# Spartan3_TestBoard.net
KiCad netlist of a schematic drawn in Altium Designer
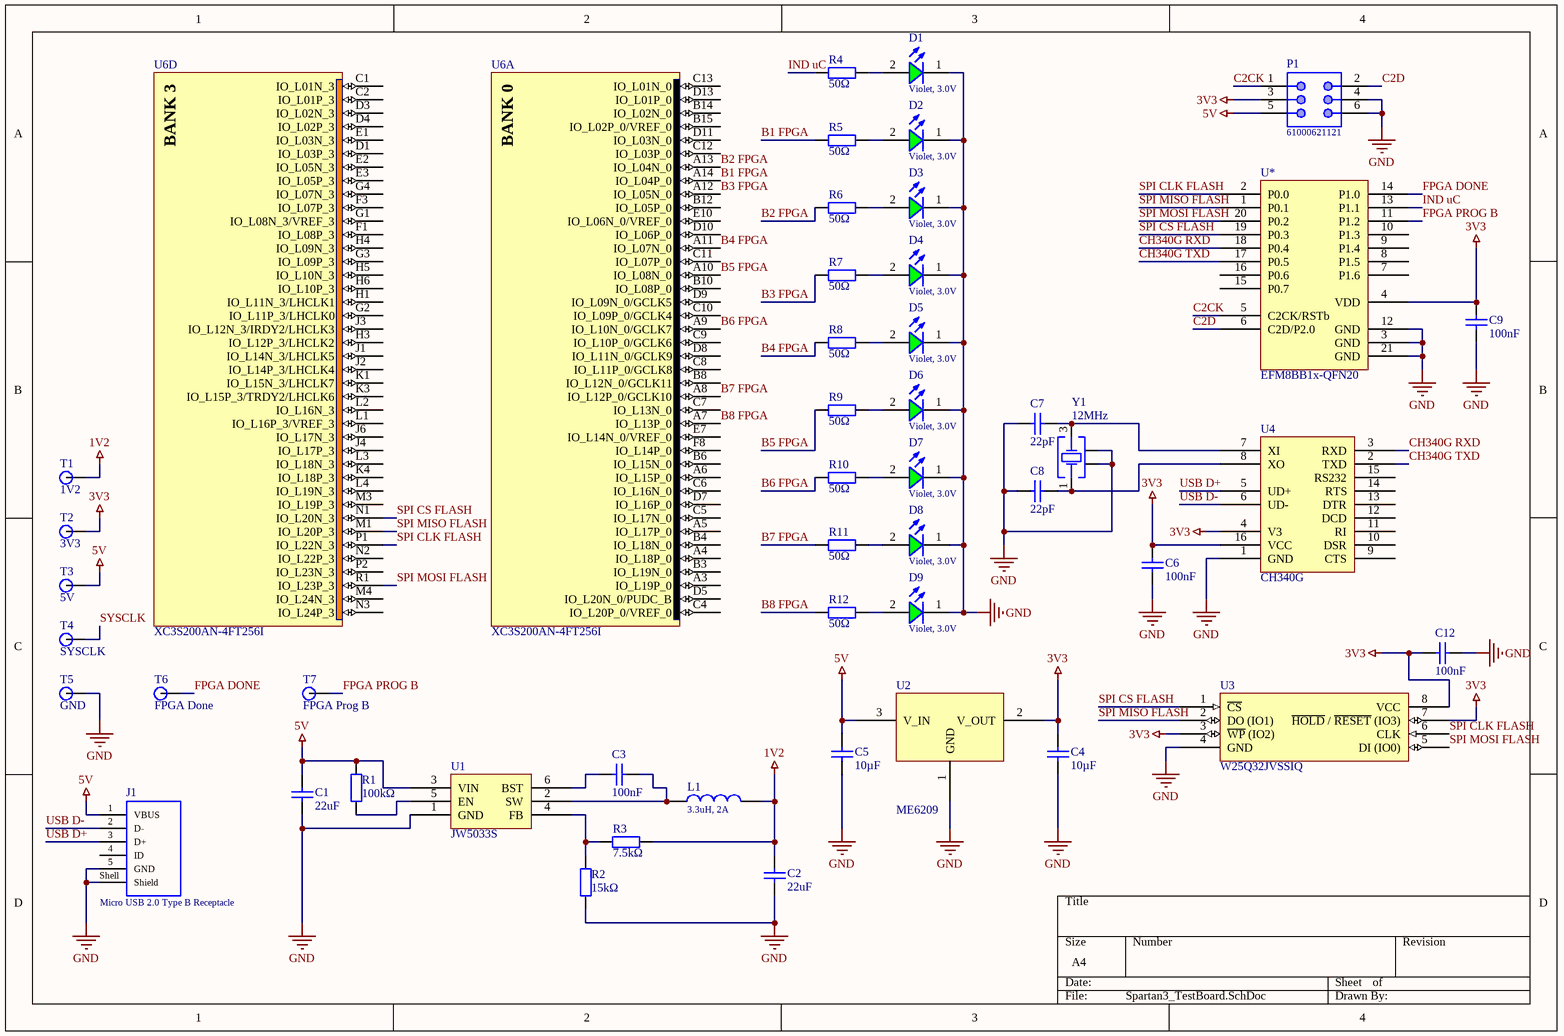
[diagram p0: Spartan3_TestBoard.SchDoc]

(export (version "E")
  (design (tool "Eeschema 10.0.6"))
  (components
    (comp (ref "C1")
      (value "22uF")
      (footprint "WCAP-CSGP_0805_H=0.8mm_Reflow")
      (description "WCAP-CSGP General Purpose Ceramic Capacitors, size 0805, 1.5nF, +/-5%, 16VDC")
      (fields (field (name "PART NUMBER") "885012007022") (field (name "PUBLISHER") "Wurth Elektronik"))
      (libsource (lib "Altium_WCAP-CSGP (rev19a)") (part "885012007022"))
    )
    (comp (ref "C2")
      (value "22uF")
      (footprint "WCAP-CSGP_0805_H=0.8mm_Reflow")
      (description "WCAP-CSGP General Purpose Ceramic Capacitors, size 0805, 1.5nF, +/-5%, 16VDC")
      (fields (field (name "PART NUMBER") "885012007022") (field (name "PUBLISHER") "Wurth Elektronik"))
      (libsource (lib "Altium_WCAP-CSGP (rev19a)") (part "885012007022"))
    )
    (comp (ref "C3")
      (value "100nF")
      (footprint "WCAP-CSGP_0402")
      (description "WCAP-CSGP General Purpose Ceramic Capacitors, size 0402, 100nF, +/-10%, 10VDC")
      (fields (field (name "PART NUMBER") "885012205018") (field (name "PUBLISHER") "Wurth Elektronik"))
      (libsource (lib "Altium_WCAP-CSGP (rev19a)") (part "885012205018"))
    )
    (comp (ref "C4")
      (value "10µF")
      (footprint "WCAP-CSGP_0402")
      (description "WCAP-CSGP General Purpose Ceramic Capacitors, size 0402, 100nF, +/-10%, 10VDC")
      (fields (field (name "PART NUMBER") "885012205018") (field (name "PUBLISHER") "Wurth Elektronik"))
      (libsource (lib "Altium_WCAP-CSGP (rev19a)") (part "885012205018"))
    )
    (comp (ref "C5")
      (value "10µF")
      (footprint "WCAP-CSGP_0402")
      (description "WCAP-CSGP General Purpose Ceramic Capacitors, size 0402, 100nF, +/-10%, 10VDC")
      (fields (field (name "PART NUMBER") "885012205018") (field (name "PUBLISHER") "Wurth Elektronik"))
      (libsource (lib "Altium_WCAP-CSGP (rev19a)") (part "885012205018"))
    )
    (comp (ref "C6")
      (value "100nF")
      (footprint "WCAP-CSGP_0402")
      (description "WCAP-CSGP General Purpose Ceramic Capacitors, size 0402, 100nF, +/-10%, 10VDC")
      (fields (field (name "PART NUMBER") "885012205018") (field (name "PUBLISHER") "Wurth Elektronik"))
      (libsource (lib "Altium_WCAP-CSGP (rev19a)") (part "885012205018"))
    )
    (comp (ref "C7")
      (value "22pF")
      (footprint "WCAP-CSGP_0402")
      (description "WCAP-CSGP General Purpose Ceramic Capacitors, size 0402, 100nF, +/-10%, 10VDC")
      (fields (field (name "PART NUMBER") "885012205018") (field (name "PUBLISHER") "Wurth Elektronik"))
      (libsource (lib "Altium_WCAP-CSGP (rev19a)") (part "885012205018"))
    )
    (comp (ref "C8")
      (value "22pF")
      (footprint "WCAP-CSGP_0402")
      (description "WCAP-CSGP General Purpose Ceramic Capacitors, size 0402, 100nF, +/-10%, 10VDC")
      (fields (field (name "PART NUMBER") "885012205018") (field (name "PUBLISHER") "Wurth Elektronik"))
      (libsource (lib "Altium_WCAP-CSGP (rev19a)") (part "885012205018"))
    )
    (comp (ref "C9")
      (value "100nF")
      (footprint "WCAP-CSGP_0402")
      (description "WCAP-CSGP General Purpose Ceramic Capacitors, size 0402, 100nF, +/-10%, 10VDC")
      (fields (field (name "PART NUMBER") "885012205018") (field (name "PUBLISHER") "Wurth Elektronik"))
      (libsource (lib "Altium_WCAP-CSGP (rev19a)") (part "885012205018"))
    )
    (comp (ref "C12")
      (value "100nF")
      (footprint "WCAP-CSGP_0402")
      (description "WCAP-CSGP General Purpose Ceramic Capacitors, size 0402, 100nF, +/-10%, 10VDC")
      (fields (field (name "PART NUMBER") "885012205018") (field (name "PUBLISHER") "Wurth Elektronik"))
      (libsource (lib "Altium_WCAP-CSGP (rev19a)") (part "885012205018"))
    )
    (comp (ref "D1")
      (value "Violet, 3.0V")
      (footprint "WL-SMCW_0603_H=0.7mm")
      (description "WL-SMCW SMT Mono-color Chip LED Waterclear, size 0603, Green, 3.2V, 140deg")
      (fields (field (name "PART NUMBER") "150060GS75000") (field (name "PUBLISHER") "Wurth Elektronik"))
      (libsource (lib "150060BS75000_Altium_WL-SMCW_rev20a") (part "150060GS75000"))
    )
    (comp (ref "D2")
      (value "Violet, 3.0V")
      (footprint "WL-SMCW_0603_H=0.7mm")
      (description "WL-SMCW SMT Mono-color Chip LED Waterclear, size 0603, Green, 3.2V, 140deg")
      (fields (field (name "PART NUMBER") "150060GS75000") (field (name "PUBLISHER") "Wurth Elektronik"))
      (libsource (lib "150060BS75000_Altium_WL-SMCW_rev20a") (part "150060GS75000"))
    )
    (comp (ref "D3")
      (value "Violet, 3.0V")
      (footprint "WL-SMCW_0603_H=0.7mm")
      (description "WL-SMCW SMT Mono-color Chip LED Waterclear, size 0603, Green, 3.2V, 140deg")
      (fields (field (name "PART NUMBER") "150060GS75000") (field (name "PUBLISHER") "Wurth Elektronik"))
      (libsource (lib "150060BS75000_Altium_WL-SMCW_rev20a") (part "150060GS75000"))
    )
    (comp (ref "D4")
      (value "Violet, 3.0V")
      (footprint "WL-SMCW_0603_H=0.7mm")
      (description "WL-SMCW SMT Mono-color Chip LED Waterclear, size 0603, Green, 3.2V, 140deg")
      (fields (field (name "PART NUMBER") "150060GS75000") (field (name "PUBLISHER") "Wurth Elektronik"))
      (libsource (lib "150060BS75000_Altium_WL-SMCW_rev20a") (part "150060GS75000"))
    )
    (comp (ref "D5")
      (value "Violet, 3.0V")
      (footprint "WL-SMCW_0603_H=0.7mm")
      (description "WL-SMCW SMT Mono-color Chip LED Waterclear, size 0603, Green, 3.2V, 140deg")
      (fields (field (name "PART NUMBER") "150060GS75000") (field (name "PUBLISHER") "Wurth Elektronik"))
      (libsource (lib "150060BS75000_Altium_WL-SMCW_rev20a") (part "150060GS75000"))
    )
    (comp (ref "D6")
      (value "Violet, 3.0V")
      (footprint "WL-SMCW_0603_H=0.7mm")
      (description "WL-SMCW SMT Mono-color Chip LED Waterclear, size 0603, Green, 3.2V, 140deg")
      (fields (field (name "PART NUMBER") "150060GS75000") (field (name "PUBLISHER") "Wurth Elektronik"))
      (libsource (lib "150060BS75000_Altium_WL-SMCW_rev20a") (part "150060GS75000"))
    )
    (comp (ref "D7")
      (value "Violet, 3.0V")
      (footprint "WL-SMCW_0603_H=0.7mm")
      (description "WL-SMCW SMT Mono-color Chip LED Waterclear, size 0603, Green, 3.2V, 140deg")
      (fields (field (name "PART NUMBER") "150060GS75000") (field (name "PUBLISHER") "Wurth Elektronik"))
      (libsource (lib "150060BS75000_Altium_WL-SMCW_rev20a") (part "150060GS75000"))
    )
    (comp (ref "D8")
      (value "Violet, 3.0V")
      (footprint "WL-SMCW_0603_H=0.7mm")
      (description "WL-SMCW SMT Mono-color Chip LED Waterclear, size 0603, Green, 3.2V, 140deg")
      (fields (field (name "PART NUMBER") "150060GS75000") (field (name "PUBLISHER") "Wurth Elektronik"))
      (libsource (lib "150060BS75000_Altium_WL-SMCW_rev20a") (part "150060GS75000"))
    )
    (comp (ref "D9")
      (value "Violet, 3.0V")
      (footprint "WL-SMCW_0603_H=0.7mm")
      (description "WL-SMCW SMT Mono-color Chip LED Waterclear, size 0603, Green, 3.2V, 140deg")
      (fields (field (name "PART NUMBER") "150060GS75000") (field (name "PUBLISHER") "Wurth Elektronik"))
      (libsource (lib "150060BS75000_Altium_WL-SMCW_rev20a") (part "150060GS75000"))
    )
    (comp (ref "J1")
      (value "Micro USB 2.0 Type B Receptacle")
      (footprint "629105136821")
      (description "Micro USB 2.0 Type B, Receptacle, Horizontal, SMT")
      (fields
        (field (name "MANUFACTURER") "Wurth Elektronik")
        (field (name "MANUFACTURER PART NUMBER") "629105136821")
      )
      (libsource (lib "Altium_WR-USB (rev21a)") (part "629105136821"))
    )
    (comp (ref "L1")
      (value "3.3uH, 2A")
      (footprint "WE-PD2_5848")
      (description "WE-PD2 SMT Power Inductor, size 5848, 3.3uH, 4A")
      (fields
        (field (name "MANUFACTURER") "Wurth Elektronik")
        (field (name "MANUFACTURER PART NUMBER") "744774033")
      )
      (libsource (lib "744774022_Altium_WE-PD2_rev20a") (part "744774033"))
    )
    (comp (ref "P1")
      (value "61000621121")
      (footprint "61000621121")
      (description "WR-PHD Pin Header, SMT, pitch 2.54mm, Dual Row, Vertical, 6p")
      (fields (field (name "MANUFACTURER") "Wurth Elektronik"))
      (libsource (lib "Altium_WR-PHD (rev20a)") (part "61000621121"))
    )
    (comp (ref "R1")
      (value "100kΩ")
      (footprint "WRIS-PSMB_0805_H=0.35mm")
      (description "WRIS-PSMB Metal Plate Resistors, size 0805, 5mOhm, +/-1%, 0.5W")
      (fields (field (name "PART NUMBER") "580060720003") (field (name "PUBLISHER") "Wurth Elektronik"))
      (libsource (lib "") (part "580060720003_1"))
    )
    (comp (ref "R2")
      (value "15kΩ")
      (footprint "WRIS-PSMB_0805_H=0.35mm")
      (description "WRIS-PSMB Metal Plate Resistors, size 0805, 5mOhm, +/-1%, 0.5W")
      (fields (field (name "PART NUMBER") "580060720003") (field (name "PUBLISHER") "Wurth Elektronik"))
      (libsource (lib "") (part "580060720003_2"))
    )
    (comp (ref "R3")
      (value "7.5kΩ")
      (footprint "WRIS-PSMB_0805_H=0.35mm")
      (description "WRIS-PSMB Metal Plate Resistors, size 0805, 5mOhm, +/-1%, 0.5W")
      (fields (field (name "PART NUMBER") "580060720003") (field (name "PUBLISHER") "Wurth Elektronik"))
      (libsource (lib "Altium_WRIS-PSMB (rev19a)") (part "580060720003"))
    )
    (comp (ref "R4")
      (value "50Ω")
      (footprint "WRIS-PSMB_0805_H=0.35mm")
      (description "WRIS-PSMB Metal Plate Resistors, size 0805, 5mOhm, +/-1%, 0.5W")
      (fields (field (name "PART NUMBER") "580060720003") (field (name "PUBLISHER") "Wurth Elektronik"))
      (libsource (lib "Altium_WRIS-PSMB (rev19a)") (part "580060720003"))
    )
    (comp (ref "R5")
      (value "50Ω")
      (footprint "WRIS-PSMB_0805_H=0.35mm")
      (description "WRIS-PSMB Metal Plate Resistors, size 0805, 5mOhm, +/-1%, 0.5W")
      (fields (field (name "PART NUMBER") "580060720003") (field (name "PUBLISHER") "Wurth Elektronik"))
      (libsource (lib "Altium_WRIS-PSMB (rev19a)") (part "580060720003"))
    )
    (comp (ref "R6")
      (value "50Ω")
      (footprint "WRIS-PSMB_0805_H=0.35mm")
      (description "WRIS-PSMB Metal Plate Resistors, size 0805, 5mOhm, +/-1%, 0.5W")
      (fields (field (name "PART NUMBER") "580060720003") (field (name "PUBLISHER") "Wurth Elektronik"))
      (libsource (lib "Altium_WRIS-PSMB (rev19a)") (part "580060720003"))
    )
    (comp (ref "R7")
      (value "50Ω")
      (footprint "WRIS-PSMB_0805_H=0.35mm")
      (description "WRIS-PSMB Metal Plate Resistors, size 0805, 5mOhm, +/-1%, 0.5W")
      (fields (field (name "PART NUMBER") "580060720003") (field (name "PUBLISHER") "Wurth Elektronik"))
      (libsource (lib "Altium_WRIS-PSMB (rev19a)") (part "580060720003"))
    )
    (comp (ref "R8")
      (value "50Ω")
      (footprint "WRIS-PSMB_0805_H=0.35mm")
      (description "WRIS-PSMB Metal Plate Resistors, size 0805, 5mOhm, +/-1%, 0.5W")
      (fields (field (name "PART NUMBER") "580060720003") (field (name "PUBLISHER") "Wurth Elektronik"))
      (libsource (lib "Altium_WRIS-PSMB (rev19a)") (part "580060720003"))
    )
    (comp (ref "R9")
      (value "50Ω")
      (footprint "WRIS-PSMB_0805_H=0.35mm")
      (description "WRIS-PSMB Metal Plate Resistors, size 0805, 5mOhm, +/-1%, 0.5W")
      (fields (field (name "PART NUMBER") "580060720003") (field (name "PUBLISHER") "Wurth Elektronik"))
      (libsource (lib "Altium_WRIS-PSMB (rev19a)") (part "580060720003"))
    )
    (comp (ref "R10")
      (value "50Ω")
      (footprint "WRIS-PSMB_0805_H=0.35mm")
      (description "WRIS-PSMB Metal Plate Resistors, size 0805, 5mOhm, +/-1%, 0.5W")
      (fields (field (name "PART NUMBER") "580060720003") (field (name "PUBLISHER") "Wurth Elektronik"))
      (libsource (lib "Altium_WRIS-PSMB (rev19a)") (part "580060720003"))
    )
    (comp (ref "R11")
      (value "50Ω")
      (footprint "WRIS-PSMB_0805_H=0.35mm")
      (description "WRIS-PSMB Metal Plate Resistors, size 0805, 5mOhm, +/-1%, 0.5W")
      (fields (field (name "PART NUMBER") "580060720003") (field (name "PUBLISHER") "Wurth Elektronik"))
      (libsource (lib "Altium_WRIS-PSMB (rev19a)") (part "580060720003"))
    )
    (comp (ref "R12")
      (value "50Ω")
      (footprint "WRIS-PSMB_0805_H=0.35mm")
      (description "WRIS-PSMB Metal Plate Resistors, size 0805, 5mOhm, +/-1%, 0.5W")
      (fields (field (name "PART NUMBER") "580060720003") (field (name "PUBLISHER") "Wurth Elektronik"))
      (libsource (lib "Altium_WRIS-PSMB (rev19a)") (part "580060720003"))
    )
    (comp (ref "T1") (value "1V2") (footprint "Testpoint") (libsource (lib "Testpoint") (part "Testpoint")))
    (comp (ref "T2") (value "3V3") (footprint "Testpoint") (libsource (lib "Testpoint") (part "Testpoint")))
    (comp (ref "T3") (value "5V") (footprint "Testpoint") (libsource (lib "Testpoint") (part "Testpoint")))
    (comp (ref "T4")
      (value "SYSCLK")
      (footprint "Testpoint")
      (libsource (lib "Testpoint") (part "Testpoint"))
    )
    (comp (ref "T5") (value "GND") (footprint "Testpoint") (libsource (lib "Testpoint") (part "Testpoint")))
    (comp (ref "T6")
      (value "FPGA Done")
      (footprint "Testpoint")
      (libsource (lib "Testpoint") (part "Testpoint"))
    )
    (comp (ref "T7")
      (value "FPGA Prog B")
      (footprint "Testpoint")
      (libsource (lib "Testpoint") (part "Testpoint"))
    )
    (comp (ref "U*")
      (value "EFM8BB1x-QFN20")
      (footprint "*QFN50P300X300X80-21N")
      (libsource (lib "EFM8BB1x_QFN20") (part "EFM8BB1x-QFN20"))
    )
    (comp (ref "U1")
      (value "JW5033S")
      (footprint "SOT95P280X110-6N")
      (description "2A Step-Down Converter")
      (libsource (lib "JW5033S") (part "JW5033S"))
    )
    (comp (ref "U2")
      (value "ME6209")
      (footprint "SOT95P285X150-3N")
      (libsource (lib "ME6209") (part "ME6209"))
    )
    (comp (ref "U3")
      (value "W25Q32JVSSIQ")
      (footprint "W25Q32JVSSIQ")
      (description "IC FLASH 32MBIT SPI/QUAD 8SOIC")
      (libsource (lib "W25Q32JVSSIQ") (part "W25Q32JVSSIQ"))
    )
    (comp (ref "U4") (value "CH340G") (footprint "CH340G") (libsource (lib "CH340G") (part "CH340G")))
    (comp (ref "U6")
      (value "XC3S200AN-4FT256I")
      (footprint "XC3S200AN-4FT256I")
      (libsource (lib "XC3S200AN-4FT256I") (part "XC3S200AN-4FT256I"))
    )
    (comp (ref "Y1")
      (value "12MHz")
      (footprint "WE-XTAL_CFPX-180")
      (description "WE-XTAL Quartz Crystal, SMT, CFPX-180, 12MHz, +/-20ppm")
      (fields
        (field (name "MANUFACTURER PART NUMBER") "830055295")
        (field (name "MANUFACTURER") "Wurth Elektronik")
      )
      (libsource (lib "Altium_WE-XTAL (rev21a)") (part "830055295"))
    )
  )
  (nets
    (net (code "1") (name "/B1 FPGA") (class "Default")
      (node (ref "R5") (pin "1") (pinfunction "1_1") (pintype "passive"))
      (node (ref "U6") (pin "A14") (pinfunction "IO_L04P_0_A14") (pintype "bidirectional"))
    )
    (net (code "2") (name "/B2 FPGA") (class "Default")
      (node (ref "R6") (pin "1") (pinfunction "1_1") (pintype "passive"))
      (node (ref "U6") (pin "A13") (pinfunction "IO_L04N_0_A13") (pintype "bidirectional"))
    )
    (net (code "3") (name "/B3 FPGA") (class "Default")
      (node (ref "R7") (pin "1") (pinfunction "1_1") (pintype "passive"))
      (node (ref "U6") (pin "A12") (pinfunction "IO_L05N_0_A12") (pintype "bidirectional"))
    )
    (net (code "4") (name "/B4 FPGA") (class "Default")
      (node (ref "R8") (pin "1") (pinfunction "1_1") (pintype "passive"))
      (node (ref "U6") (pin "A11") (pinfunction "IO_L07N_0_A11") (pintype "bidirectional"))
    )
    (net (code "5") (name "/B5 FPGA") (class "Default")
      (node (ref "R9") (pin "1") (pinfunction "1_1") (pintype "passive"))
      (node (ref "U6") (pin "A10") (pinfunction "IO_L08N_0_A10") (pintype "bidirectional"))
    )
    (net (code "6") (name "/B6 FPGA") (class "Default")
      (node (ref "R10") (pin "1") (pinfunction "1_1") (pintype "passive"))
      (node (ref "U6") (pin "A9") (pinfunction "IO_L10N_0/GCLK7_A9") (pintype "bidirectional"))
    )
    (net (code "7") (name "/B7 FPGA") (class "Default")
      (node (ref "R11") (pin "1") (pinfunction "1_1") (pintype "passive"))
      (node (ref "U6") (pin "A8") (pinfunction "IO_L12P_0/GCLK10_A8") (pintype "bidirectional"))
    )
    (net (code "8") (name "/B8 FPGA") (class "Default")
      (node (ref "R12") (pin "1") (pinfunction "1_1") (pintype "passive"))
      (node (ref "U6") (pin "A7") (pinfunction "IO_L13P_0_A7") (pintype "bidirectional"))
    )
    (net (code "9") (name "/C2CK") (class "Default")
      (node (ref "P1") (pin "1") (pinfunction "1_1") (pintype "passive"))
      (node (ref "U*") (pin "5") (pinfunction "C2CK/RSTb_5") (pintype "passive"))
    )
    (net (code "10") (name "/C2D") (class "Default")
      (node (ref "P1") (pin "2") (pinfunction "2_2") (pintype "passive"))
      (node (ref "U*") (pin "6") (pinfunction "C2D/P2.0_6") (pintype "passive"))
    )
    (net (code "11") (name "/CH340G RXD") (class "Default")
      (node (ref "U*") (pin "18") (pinfunction "P0.4_18") (pintype "passive"))
      (node (ref "U4") (pin "3") (pinfunction "RXD_3") (pintype "passive"))
    )
    (net (code "12") (name "/CH340G TXD") (class "Default")
      (node (ref "U*") (pin "17") (pinfunction "P0.5_17") (pintype "passive"))
      (node (ref "U4") (pin "2") (pinfunction "TXD_2") (pintype "passive"))
    )
    (net (code "13") (name "/FPGA DONE") (class "Default")
      (node (ref "T6") (pin "1") (pinfunction "1_1") (pintype "passive"))
      (node (ref "U*") (pin "14") (pinfunction "P1.0_14") (pintype "passive"))
    )
    (net (code "14") (name "/FPGA PROG B") (class "Default")
      (node (ref "T7") (pin "1") (pinfunction "1_1") (pintype "passive"))
      (node (ref "U*") (pin "11") (pinfunction "P1.2_11") (pintype "passive"))
    )
    (net (code "15") (name "/IND uC") (class "Default")
      (node (ref "R4") (pin "1") (pinfunction "1_1") (pintype "passive"))
      (node (ref "U*") (pin "13") (pinfunction "P1.1_13") (pintype "passive"))
    )
    (net (code "16") (name "/SPI CLK FLASH") (class "Default")
      (node (ref "U*") (pin "2") (pinfunction "P0.0_2") (pintype "passive"))
      (node (ref "U3") (pin "6") (pinfunction "CLK_6") (pintype "input"))
      (node (ref "U6") (pin "P1") (pinfunction "IO_L22N_3_P1") (pintype "bidirectional"))
    )
    (net (code "17") (name "/SPI CS FLASH") (class "Default")
      (node (ref "U*") (pin "19") (pinfunction "P0.3_19") (pintype "passive"))
      (node (ref "U3") (pin "1") (pinfunction "~{CS}_1") (pintype "input"))
      (node (ref "U6") (pin "N1") (pinfunction "IO_L20N_3_N1") (pintype "bidirectional"))
    )
    (net (code "18") (name "/SPI MISO FLASH") (class "Default")
      (node (ref "U*") (pin "1") (pinfunction "P0.1_1") (pintype "passive"))
      (node (ref "U3") (pin "2") (pinfunction "DO_(IO1)_2") (pintype "bidirectional"))
      (node (ref "U6") (pin "M1") (pinfunction "IO_L20P_3_M1") (pintype "bidirectional"))
    )
    (net (code "19") (name "/SPI MOSI FLASH") (class "Default")
      (node (ref "U*") (pin "20") (pinfunction "P0.2_20") (pintype "passive"))
      (node (ref "U3") (pin "5") (pinfunction "DI_(IO0)_5") (pintype "bidirectional"))
      (node (ref "U6") (pin "R1") (pinfunction "IO_L23P_3_R1") (pintype "bidirectional"))
    )
    (net (code "20") (name "/SYSCLK") (class "Default")
      (node (ref "T4") (pin "1") (pinfunction "1_1") (pintype "passive"))
    )
    (net (code "21") (name "/USB D+") (class "Default")
      (node (ref "J1") (pin "3") (pinfunction "D+_3") (pintype "passive"))
      (node (ref "U4") (pin "5") (pinfunction "UD+_5") (pintype "passive"))
    )
    (net (code "22") (name "/USB D-") (class "Default")
      (node (ref "J1") (pin "2") (pinfunction "D-_2") (pintype "passive"))
      (node (ref "U4") (pin "6") (pinfunction "UD-_6") (pintype "passive"))
    )
    (net (code "23") (name "1V2") (class "Default")
      (node (ref "C2") (pin "2") (pinfunction "2_2") (pintype "passive"))
      (node (ref "L1") (pin "2") (pinfunction "2_2") (pintype "passive"))
      (node (ref "R3") (pin "2") (pinfunction "2_2") (pintype "passive"))
      (node (ref "T1") (pin "1") (pinfunction "1_1") (pintype "passive"))
    )
    (net (code "24") (name "3V3") (class "Default")
      (node (ref "C12") (pin "1") (pinfunction "1_1") (pintype "passive"))
      (node (ref "C4") (pin "2") (pinfunction "2_2") (pintype "passive"))
      (node (ref "C6") (pin "2") (pinfunction "2_2") (pintype "passive"))
      (node (ref "C9") (pin "1") (pinfunction "1_1") (pintype "passive"))
      (node (ref "P1") (pin "3") (pinfunction "3_3") (pintype "passive"))
      (node (ref "T2") (pin "1") (pinfunction "1_1") (pintype "passive"))
      (node (ref "U*") (pin "4") (pinfunction "VDD_4") (pintype "passive"))
      (node (ref "U2") (pin "2") (pinfunction "V_OUT_2") (pintype "passive"))
      (node (ref "U3") (pin "3") (pinfunction "~{WP}_(IO2)_3") (pintype "bidirectional"))
      (node (ref "U3") (pin "7") (pinfunction "~{HOLD}_/_~{RESET}_(IO3)_7") (pintype "bidirectional"))
      (node (ref "U3") (pin "8") (pinfunction "VCC_8") (pintype "power_in"))
      (node (ref "U4") (pin "16") (pinfunction "VCC_16") (pintype "passive"))
      (node (ref "U4") (pin "4") (pinfunction "V3_4") (pintype "passive"))
    )
    (net (code "25") (name "5V") (class "Default")
      (node (ref "C1") (pin "2") (pinfunction "2_2") (pintype "passive"))
      (node (ref "C5") (pin "2") (pinfunction "2_2") (pintype "passive"))
      (node (ref "J1") (pin "1") (pinfunction "VBUS_1") (pintype "passive"))
      (node (ref "P1") (pin "5") (pinfunction "5_5") (pintype "passive"))
      (node (ref "R1") (pin "1") (pinfunction "1_1") (pintype "passive"))
      (node (ref "T3") (pin "1") (pinfunction "1_1") (pintype "passive"))
      (node (ref "U1") (pin "3") (pinfunction "VIN_3") (pintype "passive"))
      (node (ref "U2") (pin "3") (pinfunction "V_IN_3") (pintype "passive"))
    )
    (net (code "26") (name "GND") (class "Default")
      (node (ref "C1") (pin "1") (pinfunction "1_1") (pintype "passive"))
      (node (ref "C12") (pin "2") (pinfunction "2_2") (pintype "passive"))
      (node (ref "C2") (pin "1") (pinfunction "1_1") (pintype "passive"))
      (node (ref "C4") (pin "1") (pinfunction "1_1") (pintype "passive"))
      (node (ref "C5") (pin "1") (pinfunction "1_1") (pintype "passive"))
      (node (ref "C6") (pin "1") (pinfunction "1_1") (pintype "passive"))
      (node (ref "C7") (pin "2") (pinfunction "2_2") (pintype "passive"))
      (node (ref "C8") (pin "2") (pinfunction "2_2") (pintype "passive"))
      (node (ref "C9") (pin "2") (pinfunction "2_2") (pintype "passive"))
      (node (ref "D1") (pin "1") (pinfunction "K_1") (pintype "passive"))
      (node (ref "D2") (pin "1") (pinfunction "K_1") (pintype "passive"))
      (node (ref "D3") (pin "1") (pinfunction "K_1") (pintype "passive"))
      (node (ref "D4") (pin "1") (pinfunction "K_1") (pintype "passive"))
      (node (ref "D5") (pin "1") (pinfunction "K_1") (pintype "passive"))
      (node (ref "D6") (pin "1") (pinfunction "K_1") (pintype "passive"))
      (node (ref "D7") (pin "1") (pinfunction "K_1") (pintype "passive"))
      (node (ref "D8") (pin "1") (pinfunction "K_1") (pintype "passive"))
      (node (ref "D9") (pin "1") (pinfunction "K_1") (pintype "passive"))
      (node (ref "J1") (pin "5") (pinfunction "GND_5") (pintype "passive"))
      (node (ref "J1") (pin "Shell") (pinfunction "Shield_Shell") (pintype "passive"))
      (node (ref "P1") (pin "4") (pinfunction "4_4") (pintype "passive"))
      (node (ref "P1") (pin "6") (pinfunction "6_6") (pintype "passive"))
      (node (ref "R2") (pin "1") (pinfunction "1_1") (pintype "passive"))
      (node (ref "T5") (pin "1") (pinfunction "1_1") (pintype "passive"))
      (node (ref "U*") (pin "12") (pinfunction "GND_12") (pintype "passive"))
      (node (ref "U*") (pin "21") (pinfunction "GND_21") (pintype "passive"))
      (node (ref "U*") (pin "3") (pinfunction "GND_3") (pintype "passive"))
      (node (ref "U1") (pin "1") (pinfunction "GND_1") (pintype "passive"))
      (node (ref "U2") (pin "1") (pinfunction "GND_1") (pintype "passive"))
      (node (ref "U3") (pin "4") (pinfunction "GND_4") (pintype "passive"))
      (node (ref "U4") (pin "1") (pinfunction "GND_1") (pintype "passive"))
      (node (ref "Y1") (pin "2") (pinfunction "GND_2") (pintype "passive"))
      (node (ref "Y1") (pin "4") (pinfunction "GND_4") (pintype "passive"))
    )
    (net (code "27") (name "Net-(D1-A)") (class "Default")
      (node (ref "D1") (pin "2") (pinfunction "A_2") (pintype "passive"))
      (node (ref "R4") (pin "2") (pinfunction "2_2") (pintype "passive"))
    )
    (net (code "28") (name "Net-(D2-A)") (class "Default")
      (node (ref "D2") (pin "2") (pinfunction "A_2") (pintype "passive"))
      (node (ref "R5") (pin "2") (pinfunction "2_2") (pintype "passive"))
    )
    (net (code "29") (name "Net-(D3-A)") (class "Default")
      (node (ref "D3") (pin "2") (pinfunction "A_2") (pintype "passive"))
      (node (ref "R6") (pin "2") (pinfunction "2_2") (pintype "passive"))
    )
    (net (code "30") (name "Net-(D4-A)") (class "Default")
      (node (ref "D4") (pin "2") (pinfunction "A_2") (pintype "passive"))
      (node (ref "R7") (pin "2") (pinfunction "2_2") (pintype "passive"))
    )
    (net (code "31") (name "Net-(D5-A)") (class "Default")
      (node (ref "D5") (pin "2") (pinfunction "A_2") (pintype "passive"))
      (node (ref "R8") (pin "2") (pinfunction "2_2") (pintype "passive"))
    )
    (net (code "32") (name "Net-(D6-A)") (class "Default")
      (node (ref "D6") (pin "2") (pinfunction "A_2") (pintype "passive"))
      (node (ref "R9") (pin "2") (pinfunction "2_2") (pintype "passive"))
    )
    (net (code "33") (name "Net-(D7-A)") (class "Default")
      (node (ref "D7") (pin "2") (pinfunction "A_2") (pintype "passive"))
      (node (ref "R10") (pin "2") (pinfunction "2_2") (pintype "passive"))
    )
    (net (code "34") (name "Net-(D8-A)") (class "Default")
      (node (ref "D8") (pin "2") (pinfunction "A_2") (pintype "passive"))
      (node (ref "R11") (pin "2") (pinfunction "2_2") (pintype "passive"))
    )
    (net (code "35") (name "Net-(D9-A)") (class "Default")
      (node (ref "D9") (pin "2") (pinfunction "A_2") (pintype "passive"))
      (node (ref "R12") (pin "2") (pinfunction "2_2") (pintype "passive"))
    )
    (net (code "36") (name "Net-(U1-BST)") (class "Default")
      (node (ref "C3") (pin "2") (pinfunction "2_2") (pintype "passive"))
      (node (ref "U1") (pin "6") (pinfunction "BST_6") (pintype "passive"))
    )
    (net (code "37") (name "Net-(U1-EN)") (class "Default")
      (node (ref "R1") (pin "2") (pinfunction "2_2") (pintype "passive"))
      (node (ref "U1") (pin "5") (pinfunction "EN_5") (pintype "passive"))
    )
    (net (code "38") (name "Net-(U1-FB)") (class "Default")
      (node (ref "R2") (pin "2") (pinfunction "2_2") (pintype "passive"))
      (node (ref "R3") (pin "1") (pinfunction "1_1") (pintype "passive"))
      (node (ref "U1") (pin "4") (pinfunction "FB_4") (pintype "passive"))
    )
    (net (code "39") (name "Net-(U1-SW)") (class "Default")
      (node (ref "C3") (pin "1") (pinfunction "1_1") (pintype "passive"))
      (node (ref "L1") (pin "1") (pinfunction "1_1") (pintype "passive"))
      (node (ref "U1") (pin "2") (pinfunction "SW_2") (pintype "passive"))
    )
    (net (code "40") (name "Net-(U4-XI)") (class "Default")
      (node (ref "C7") (pin "1") (pinfunction "1_1") (pintype "passive"))
      (node (ref "U4") (pin "7") (pinfunction "XI_7") (pintype "passive"))
      (node (ref "Y1") (pin "3") (pinfunction "Crystal_3") (pintype "passive"))
    )
    (net (code "41") (name "Net-(U4-XO)") (class "Default")
      (node (ref "C8") (pin "1") (pinfunction "1_1") (pintype "passive"))
      (node (ref "U4") (pin "8") (pinfunction "XO_8") (pintype "passive"))
      (node (ref "Y1") (pin "1") (pinfunction "Crystal_1") (pintype "passive"))
    )
    (net (code "42") (name "unconnected-(J1-ID-Pad4)") (class "Default")
      (node (ref "J1") (pin "4") (pinfunction "ID_4") (pintype "passive"))
    )
    (net (code "43") (name "unconnected-(U*-P0.6-Pad16)") (class "Default")
      (node (ref "U*") (pin "16") (pinfunction "P0.6_16") (pintype "passive"))
    )
    (net (code "44") (name "unconnected-(U*-P0.7-Pad15)") (class "Default")
      (node (ref "U*") (pin "15") (pinfunction "P0.7_15") (pintype "passive"))
    )
    (net (code "45") (name "unconnected-(U*-P1.3-Pad10)") (class "Default")
      (node (ref "U*") (pin "10") (pinfunction "P1.3_10") (pintype "passive"))
    )
    (net (code "46") (name "unconnected-(U*-P1.4-Pad9)") (class "Default")
      (node (ref "U*") (pin "9") (pinfunction "P1.4_9") (pintype "passive"))
    )
    (net (code "47") (name "unconnected-(U*-P1.5-Pad8)") (class "Default")
      (node (ref "U*") (pin "8") (pinfunction "P1.5_8") (pintype "passive"))
    )
    (net (code "48") (name "unconnected-(U*-P1.6-Pad7)") (class "Default")
      (node (ref "U*") (pin "7") (pinfunction "P1.6_7") (pintype "passive"))
    )
    (net (code "49") (name "unconnected-(U4-CTS-Pad9)") (class "Default")
      (node (ref "U4") (pin "9") (pinfunction "CTS_9") (pintype "passive"))
    )
    (net (code "50") (name "unconnected-(U4-DCD-Pad12)") (class "Default")
      (node (ref "U4") (pin "12") (pinfunction "DCD_12") (pintype "passive"))
    )
    (net (code "51") (name "unconnected-(U4-DSR-Pad10)") (class "Default")
      (node (ref "U4") (pin "10") (pinfunction "DSR_10") (pintype "passive"))
    )
    (net (code "52") (name "unconnected-(U4-DTR-Pad13)") (class "Default")
      (node (ref "U4") (pin "13") (pinfunction "DTR_13") (pintype "passive"))
    )
    (net (code "53") (name "unconnected-(U4-RI-Pad11)") (class "Default")
      (node (ref "U4") (pin "11") (pinfunction "RI_11") (pintype "passive"))
    )
    (net (code "54") (name "unconnected-(U4-RS232-Pad15)") (class "Default")
      (node (ref "U4") (pin "15") (pinfunction "RS232_15") (pintype "passive"))
    )
    (net (code "55") (name "unconnected-(U4-RTS-Pad14)") (class "Default")
      (node (ref "U4") (pin "14") (pinfunction "RTS_14") (pintype "passive"))
    )
    (net (code "56") (name "unconnected-(U6A-IO_L01N_0-PadC13)") (class "Default")
      (node (ref "U6") (pin "C13") (pinfunction "IO_L01N_0_C13") (pintype "bidirectional"))
    )
    (net (code "57") (name "unconnected-(U6A-IO_L01P_0-PadD13)") (class "Default")
      (node (ref "U6") (pin "D13") (pinfunction "IO_L01P_0_D13") (pintype "bidirectional"))
    )
    (net (code "58") (name "unconnected-(U6A-IO_L02N_0-PadB14)") (class "Default")
      (node (ref "U6") (pin "B14") (pinfunction "IO_L02N_0_B14") (pintype "bidirectional"))
    )
    (net (code "59") (name "unconnected-(U6A-IO_L02P_0{slash}VREF_0-PadB15)") (class "Default")
      (node (ref "U6") (pin "B15") (pinfunction "IO_L02P_0/VREF_0_B15") (pintype "bidirectional"))
    )
    (net (code "60") (name "unconnected-(U6A-IO_L03N_0-PadD11)") (class "Default")
      (node (ref "U6") (pin "D11") (pinfunction "IO_L03N_0_D11") (pintype "bidirectional"))
    )
    (net (code "61") (name "unconnected-(U6A-IO_L03P_0-PadC12)") (class "Default")
      (node (ref "U6") (pin "C12") (pinfunction "IO_L03P_0_C12") (pintype "bidirectional"))
    )
    (net (code "62") (name "unconnected-(U6A-IO_L05P_0-PadB12)") (class "Default")
      (node (ref "U6") (pin "B12") (pinfunction "IO_L05P_0_B12") (pintype "bidirectional"))
    )
    (net (code "63") (name "unconnected-(U6A-IO_L06N_0{slash}VREF_0-PadE10)") (class "Default")
      (node (ref "U6") (pin "E10") (pinfunction "IO_L06N_0/VREF_0_E10") (pintype "bidirectional"))
    )
    (net (code "64") (name "unconnected-(U6A-IO_L06P_0-PadD10)") (class "Default")
      (node (ref "U6") (pin "D10") (pinfunction "IO_L06P_0_D10") (pintype "bidirectional"))
    )
    (net (code "65") (name "unconnected-(U6A-IO_L07P_0-PadC11)") (class "Default")
      (node (ref "U6") (pin "C11") (pinfunction "IO_L07P_0_C11") (pintype "bidirectional"))
    )
    (net (code "66") (name "unconnected-(U6A-IO_L08P_0-PadB10)") (class "Default")
      (node (ref "U6") (pin "B10") (pinfunction "IO_L08P_0_B10") (pintype "bidirectional"))
    )
    (net (code "67") (name "unconnected-(U6A-IO_L09N_0{slash}GCLK5-PadD9)") (class "Default")
      (node (ref "U6") (pin "D9") (pinfunction "IO_L09N_0/GCLK5_D9") (pintype "bidirectional"))
    )
    (net (code "68") (name "unconnected-(U6A-IO_L09P_0{slash}GCLK4-PadC10)") (class "Default")
      (node (ref "U6") (pin "C10") (pinfunction "IO_L09P_0/GCLK4_C10") (pintype "bidirectional"))
    )
    (net (code "69") (name "unconnected-(U6A-IO_L10P_0{slash}GCLK6-PadC9)") (class "Default")
      (node (ref "U6") (pin "C9") (pinfunction "IO_L10P_0/GCLK6_C9") (pintype "bidirectional"))
    )
    (net (code "70") (name "unconnected-(U6A-IO_L11N_0{slash}GCLK9-PadD8)") (class "Default")
      (node (ref "U6") (pin "D8") (pinfunction "IO_L11N_0/GCLK9_D8") (pintype "bidirectional"))
    )
    (net (code "71") (name "unconnected-(U6A-IO_L11P_0{slash}GCLK8-PadC8)") (class "Default")
      (node (ref "U6") (pin "C8") (pinfunction "IO_L11P_0/GCLK8_C8") (pintype "bidirectional"))
    )
    (net (code "72") (name "unconnected-(U6A-IO_L12N_0{slash}GCLK11-PadB8)") (class "Default")
      (node (ref "U6") (pin "B8") (pinfunction "IO_L12N_0/GCLK11_B8") (pintype "bidirectional"))
    )
    (net (code "73") (name "unconnected-(U6A-IO_L13N_0-PadC7)") (class "Default")
      (node (ref "U6") (pin "C7") (pinfunction "IO_L13N_0_C7") (pintype "bidirectional"))
    )
    (net (code "74") (name "unconnected-(U6A-IO_L14N_0{slash}VREF_0-PadE7)") (class "Default")
      (node (ref "U6") (pin "E7") (pinfunction "IO_L14N_0/VREF_0_E7") (pintype "bidirectional"))
    )
    (net (code "75") (name "unconnected-(U6A-IO_L14P_0-PadF8)") (class "Default")
      (node (ref "U6") (pin "F8") (pinfunction "IO_L14P_0_F8") (pintype "bidirectional"))
    )
    (net (code "76") (name "unconnected-(U6A-IO_L15N_0-PadB6)") (class "Default")
      (node (ref "U6") (pin "B6") (pinfunction "IO_L15N_0_B6") (pintype "bidirectional"))
    )
    (net (code "77") (name "unconnected-(U6A-IO_L15P_0-PadA6)") (class "Default")
      (node (ref "U6") (pin "A6") (pinfunction "IO_L15P_0_A6") (pintype "bidirectional"))
    )
    (net (code "78") (name "unconnected-(U6A-IO_L16N_0-PadC6)") (class "Default")
      (node (ref "U6") (pin "C6") (pinfunction "IO_L16N_0_C6") (pintype "bidirectional"))
    )
    (net (code "79") (name "unconnected-(U6A-IO_L16P_0-PadD7)") (class "Default")
      (node (ref "U6") (pin "D7") (pinfunction "IO_L16P_0_D7") (pintype "bidirectional"))
    )
    (net (code "80") (name "unconnected-(U6A-IO_L17N_0-PadC5)") (class "Default")
      (node (ref "U6") (pin "C5") (pinfunction "IO_L17N_0_C5") (pintype "bidirectional"))
    )
    (net (code "81") (name "unconnected-(U6A-IO_L17P_0-PadA5)") (class "Default")
      (node (ref "U6") (pin "A5") (pinfunction "IO_L17P_0_A5") (pintype "bidirectional"))
    )
    (net (code "82") (name "unconnected-(U6A-IO_L18N_0-PadB4)") (class "Default")
      (node (ref "U6") (pin "B4") (pinfunction "IO_L18N_0_B4") (pintype "bidirectional"))
    )
    (net (code "83") (name "unconnected-(U6A-IO_L18P_0-PadA4)") (class "Default")
      (node (ref "U6") (pin "A4") (pinfunction "IO_L18P_0_A4") (pintype "bidirectional"))
    )
    (net (code "84") (name "unconnected-(U6A-IO_L19N_0-PadB3)") (class "Default")
      (node (ref "U6") (pin "B3") (pinfunction "IO_L19N_0_B3") (pintype "bidirectional"))
    )
    (net (code "85") (name "unconnected-(U6A-IO_L19P_0-PadA3)") (class "Default")
      (node (ref "U6") (pin "A3") (pinfunction "IO_L19P_0_A3") (pintype "bidirectional"))
    )
    (net (code "86") (name "unconnected-(U6A-IO_L20N_0{slash}PUDC_B-PadD5)") (class "Default")
      (node (ref "U6") (pin "D5") (pinfunction "IO_L20N_0/PUDC_B_D5") (pintype "bidirectional"))
    )
    (net (code "87") (name "unconnected-(U6A-IO_L20P_0{slash}VREF_0-PadC4)") (class "Default")
      (node (ref "U6") (pin "C4") (pinfunction "IO_L20P_0/VREF_0_C4") (pintype "bidirectional"))
    )
    (net (code "88") (name "unconnected-(U6D-IO_L01N_3-PadC1)") (class "Default")
      (node (ref "U6") (pin "C1") (pinfunction "IO_L01N_3_C1") (pintype "bidirectional"))
    )
    (net (code "89") (name "unconnected-(U6D-IO_L01P_3-PadC2)") (class "Default")
      (node (ref "U6") (pin "C2") (pinfunction "IO_L01P_3_C2") (pintype "bidirectional"))
    )
    (net (code "90") (name "unconnected-(U6D-IO_L02N_3-PadD3)") (class "Default")
      (node (ref "U6") (pin "D3") (pinfunction "IO_L02N_3_D3") (pintype "bidirectional"))
    )
    (net (code "91") (name "unconnected-(U6D-IO_L02P_3-PadD4)") (class "Default")
      (node (ref "U6") (pin "D4") (pinfunction "IO_L02P_3_D4") (pintype "bidirectional"))
    )
    (net (code "92") (name "unconnected-(U6D-IO_L03N_3-PadE1)") (class "Default")
      (node (ref "U6") (pin "E1") (pinfunction "IO_L03N_3_E1") (pintype "bidirectional"))
    )
    (net (code "93") (name "unconnected-(U6D-IO_L03P_3-PadD1)") (class "Default")
      (node (ref "U6") (pin "D1") (pinfunction "IO_L03P_3_D1") (pintype "bidirectional"))
    )
    (net (code "94") (name "unconnected-(U6D-IO_L05N_3-PadE2)") (class "Default")
      (node (ref "U6") (pin "E2") (pinfunction "IO_L05N_3_E2") (pintype "bidirectional"))
    )
    (net (code "95") (name "unconnected-(U6D-IO_L05P_3-PadE3)") (class "Default")
      (node (ref "U6") (pin "E3") (pinfunction "IO_L05P_3_E3") (pintype "bidirectional"))
    )
    (net (code "96") (name "unconnected-(U6D-IO_L07N_3-PadG4)") (class "Default")
      (node (ref "U6") (pin "G4") (pinfunction "IO_L07N_3_G4") (pintype "bidirectional"))
    )
    (net (code "97") (name "unconnected-(U6D-IO_L07P_3-PadF3)") (class "Default")
      (node (ref "U6") (pin "F3") (pinfunction "IO_L07P_3_F3") (pintype "bidirectional"))
    )
    (net (code "98") (name "unconnected-(U6D-IO_L08N_3{slash}VREF_3-PadG1)") (class "Default")
      (node (ref "U6") (pin "G1") (pinfunction "IO_L08N_3/VREF_3_G1") (pintype "bidirectional"))
    )
    (net (code "99") (name "unconnected-(U6D-IO_L08P_3-PadF1)") (class "Default")
      (node (ref "U6") (pin "F1") (pinfunction "IO_L08P_3_F1") (pintype "bidirectional"))
    )
    (net (code "100") (name "unconnected-(U6D-IO_L09N_3-PadH4)") (class "Default")
      (node (ref "U6") (pin "H4") (pinfunction "IO_L09N_3_H4") (pintype "bidirectional"))
    )
    (net (code "101") (name "unconnected-(U6D-IO_L09P_3-PadG3)") (class "Default")
      (node (ref "U6") (pin "G3") (pinfunction "IO_L09P_3_G3") (pintype "bidirectional"))
    )
    (net (code "102") (name "unconnected-(U6D-IO_L10N_3-PadH5)") (class "Default")
      (node (ref "U6") (pin "H5") (pinfunction "IO_L10N_3_H5") (pintype "bidirectional"))
    )
    (net (code "103") (name "unconnected-(U6D-IO_L10P_3-PadH6)") (class "Default")
      (node (ref "U6") (pin "H6") (pinfunction "IO_L10P_3_H6") (pintype "bidirectional"))
    )
    (net (code "104") (name "unconnected-(U6D-IO_L11N_3{slash}LHCLK1-PadH1)") (class "Default")
      (node (ref "U6") (pin "H1") (pinfunction "IO_L11N_3/LHCLK1_H1") (pintype "bidirectional"))
    )
    (net (code "105") (name "unconnected-(U6D-IO_L11P_3{slash}LHCLK0-PadG2)") (class "Default")
      (node (ref "U6") (pin "G2") (pinfunction "IO_L11P_3/LHCLK0_G2") (pintype "bidirectional"))
    )
    (net (code "106") (name "unconnected-(U6D-IO_L12N_3{slash}IRDY2{slash}LHCLK3-PadJ3)") (class "Default")
      (node (ref "U6") (pin "J3") (pinfunction "IO_L12N_3/IRDY2/LHCLK3_J3") (pintype "bidirectional"))
    )
    (net (code "107") (name "unconnected-(U6D-IO_L12P_3{slash}LHCLK2-PadH3)") (class "Default")
      (node (ref "U6") (pin "H3") (pinfunction "IO_L12P_3/LHCLK2_H3") (pintype "bidirectional"))
    )
    (net (code "108") (name "unconnected-(U6D-IO_L14N_3{slash}LHCLK5-PadJ1)") (class "Default")
      (node (ref "U6") (pin "J1") (pinfunction "IO_L14N_3/LHCLK5_J1") (pintype "bidirectional"))
    )
    (net (code "109") (name "unconnected-(U6D-IO_L14P_3{slash}LHCLK4-PadJ2)") (class "Default")
      (node (ref "U6") (pin "J2") (pinfunction "IO_L14P_3/LHCLK4_J2") (pintype "bidirectional"))
    )
    (net (code "110") (name "unconnected-(U6D-IO_L15N_3{slash}LHCLK7-PadK1)") (class "Default")
      (node (ref "U6") (pin "K1") (pinfunction "IO_L15N_3/LHCLK7_K1") (pintype "bidirectional"))
    )
    (net (code "111") (name "unconnected-(U6D-IO_L15P_3{slash}TRDY2{slash}LHCLK6-PadK3)") (class "Default")
      (node (ref "U6") (pin "K3") (pinfunction "IO_L15P_3/TRDY2/LHCLK6_K3") (pintype "bidirectional"))
    )
    (net (code "112") (name "unconnected-(U6D-IO_L16N_3-PadL2)") (class "Default")
      (node (ref "U6") (pin "L2") (pinfunction "IO_L16N_3_L2") (pintype "bidirectional"))
    )
    (net (code "113") (name "unconnected-(U6D-IO_L16P_3{slash}VREF_3-PadL1)") (class "Default")
      (node (ref "U6") (pin "L1") (pinfunction "IO_L16P_3/VREF_3_L1") (pintype "bidirectional"))
    )
    (net (code "114") (name "unconnected-(U6D-IO_L17N_3-PadJ6)") (class "Default")
      (node (ref "U6") (pin "J6") (pinfunction "IO_L17N_3_J6") (pintype "bidirectional"))
    )
    (net (code "115") (name "unconnected-(U6D-IO_L17P_3-PadJ4)") (class "Default")
      (node (ref "U6") (pin "J4") (pinfunction "IO_L17P_3_J4") (pintype "bidirectional"))
    )
    (net (code "116") (name "unconnected-(U6D-IO_L18N_3-PadL3)") (class "Default")
      (node (ref "U6") (pin "L3") (pinfunction "IO_L18N_3_L3") (pintype "bidirectional"))
    )
    (net (code "117") (name "unconnected-(U6D-IO_L18P_3-PadK4)") (class "Default")
      (node (ref "U6") (pin "K4") (pinfunction "IO_L18P_3_K4") (pintype "bidirectional"))
    )
    (net (code "118") (name "unconnected-(U6D-IO_L19N_3-PadL4)") (class "Default")
      (node (ref "U6") (pin "L4") (pinfunction "IO_L19N_3_L4") (pintype "bidirectional"))
    )
    (net (code "119") (name "unconnected-(U6D-IO_L19P_3-PadM3)") (class "Default")
      (node (ref "U6") (pin "M3") (pinfunction "IO_L19P_3_M3") (pintype "bidirectional"))
    )
    (net (code "120") (name "unconnected-(U6D-IO_L22P_3-PadN2)") (class "Default")
      (node (ref "U6") (pin "N2") (pinfunction "IO_L22P_3_N2") (pintype "bidirectional"))
    )
    (net (code "121") (name "unconnected-(U6D-IO_L23N_3-PadP2)") (class "Default")
      (node (ref "U6") (pin "P2") (pinfunction "IO_L23N_3_P2") (pintype "bidirectional"))
    )
    (net (code "122") (name "unconnected-(U6D-IO_L24N_3-PadM4)") (class "Default")
      (node (ref "U6") (pin "M4") (pinfunction "IO_L24N_3_M4") (pintype "bidirectional"))
    )
    (net (code "123") (name "unconnected-(U6D-IO_L24P_3-PadN3)") (class "Default")
      (node (ref "U6") (pin "N3") (pinfunction "IO_L24P_3_N3") (pintype "bidirectional"))
    )
  )
)
